# Ethernet_Sheet.net
KiCad netlist of a schematic drawn in Altium Designer
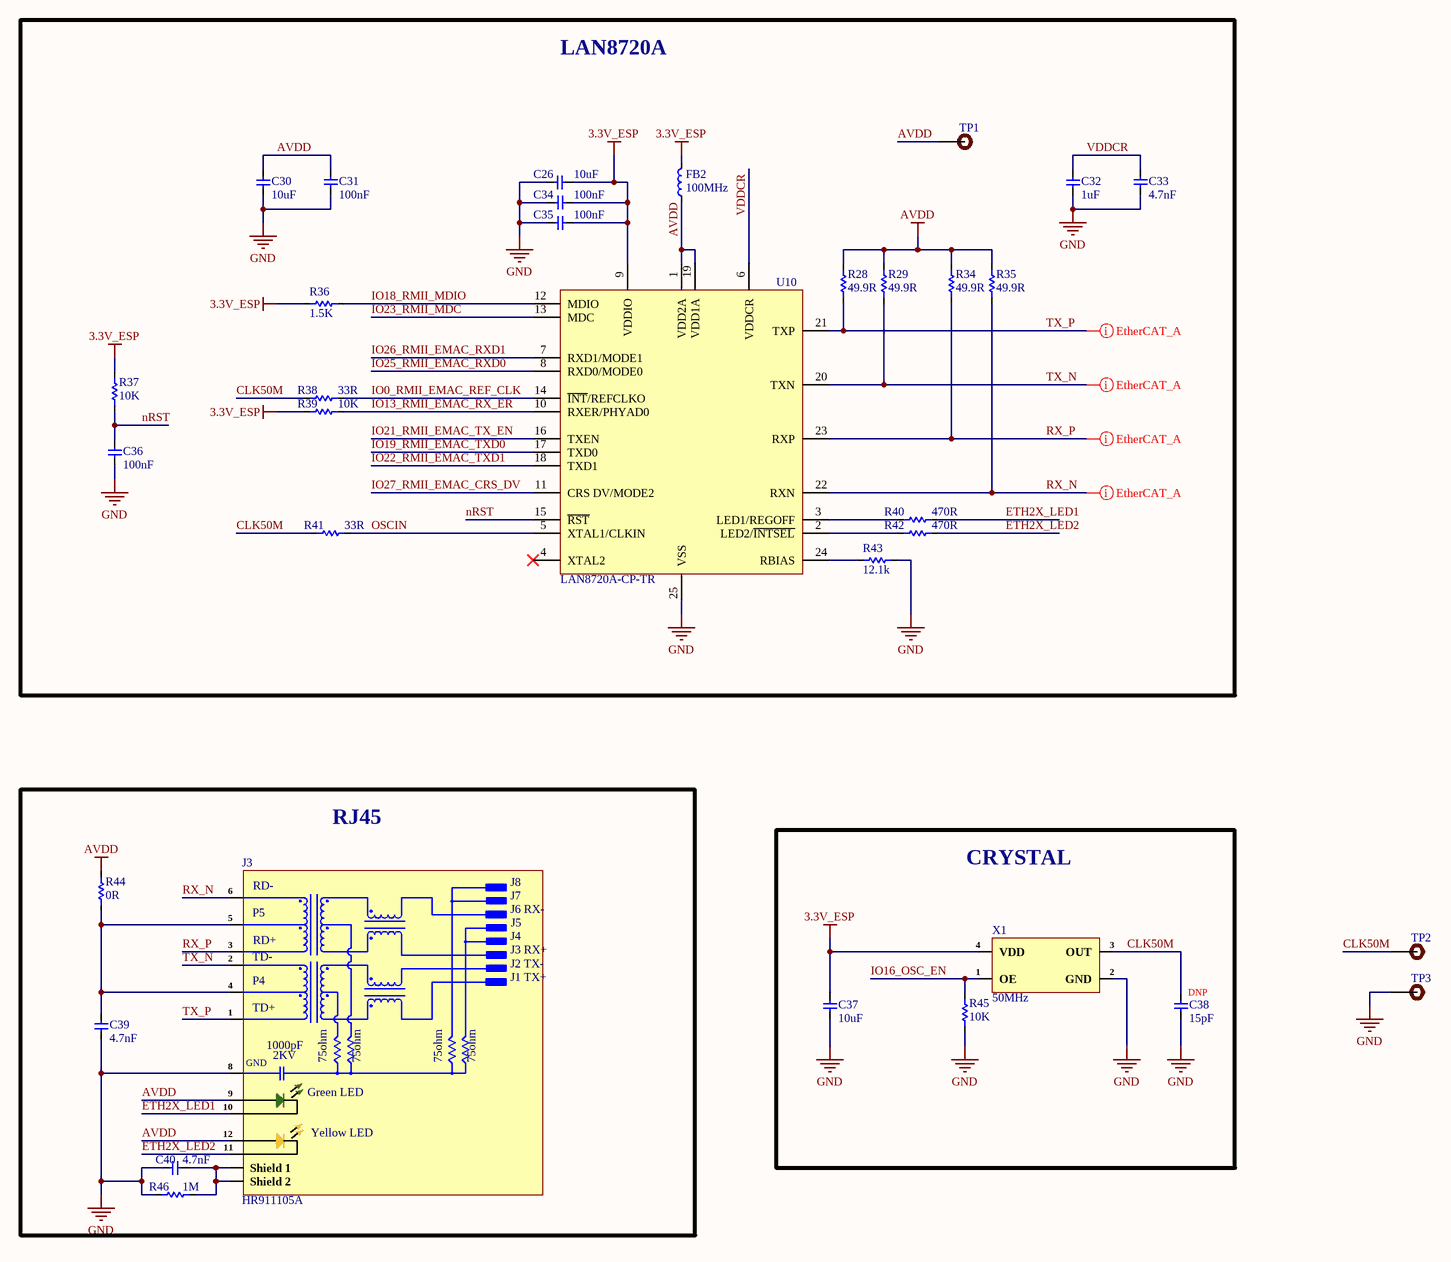
[diagram p0: Ethernet_Sheet.SchDoc]

(export (version "E")
  (design (tool "Eeschema 10.0.6"))
  (components
    (comp (ref "C26")
      (value "10uF")
      (footprint "Cap-0603")
      (description "CAP CER 10UF 25V X5R 0603")
      (fields
        (field (name "MANUFACTURER") "Samsung")
        (field (name "MANUFACTURER PART NUMBER") "CL10A106MA8NRNC")
      )
      (libsource (lib "eSpark Libraries") (part "CL10A106MA8NRNC"))
    )
    (comp (ref "C30")
      (value "10uF")
      (footprint "Cap-0603")
      (description "CAP CER 10UF 25V X5R 0603")
      (fields
        (field (name "MANUFACTURER") "Samsung")
        (field (name "MANUFACTURER PART NUMBER") "CL10A106MA8NRNC")
      )
      (libsource (lib "eSpark Libraries") (part "CL10A106MA8NRNC"))
    )
    (comp (ref "C31")
      (value "100nF")
      (footprint "cap-0402")
      (description "CAP CER 0.1UF 50V X7R 0402")
      (fields
        (field (name "MANUFACTURER") "TDK")
        (field (name "MANUFACTURER PART NUMBER") "C1005X7R1H104KT000F")
      )
      (libsource (lib "eSpark Libraries") (part "C1005X7R1H104KT000F"))
    )
    (comp (ref "C32")
      (value "1uF")
      (footprint "Cap-0402")
      (description "CAP CER 1UF 16V X5R 0402")
      (fields
        (field (name "MANUFACTURER") "Yageo")
        (field (name "MANUFACTURER PART NUMBER") "CC0402KRX5R7BB105")
      )
      (libsource (lib "eSpark Libraries") (part "CC0402KRX5R7BB105"))
    )
    (comp (ref "C33")
      (value "4.7nF")
      (footprint "Cap-0402")
      (description "CAP CER 4700PF 50V X7R 0402")
      (fields
        (field (name "MANUFACTURER") "Yageo")
        (field (name "MANUFACTURER PART NUMBER") "CC0402KRX7R9BB472")
      )
      (libsource (lib "eSpark Libraries") (part "CC0402KRX7R9BB472"))
    )
    (comp (ref "C34")
      (value "100nF")
      (footprint "cap-0402")
      (description "CAP CER 0.1UF 50V X7R 0402")
      (fields
        (field (name "MANUFACTURER") "TDK")
        (field (name "MANUFACTURER PART NUMBER") "C1005X7R1H104KT000F")
      )
      (libsource (lib "eSpark Libraries") (part "C1005X7R1H104KT000F"))
    )
    (comp (ref "C35")
      (value "100nF")
      (footprint "cap-0402")
      (description "CAP CER 0.1UF 50V X7R 0402")
      (fields
        (field (name "MANUFACTURER") "TDK")
        (field (name "MANUFACTURER PART NUMBER") "C1005X7R1H104KT000F")
      )
      (libsource (lib "eSpark Libraries") (part "C1005X7R1H104KT000F"))
    )
    (comp (ref "C36")
      (value "100nF")
      (footprint "cap-0402")
      (description "CAP CER 0.1UF 50V X7R 0402")
      (fields
        (field (name "MANUFACTURER") "TDK")
        (field (name "MANUFACTURER PART NUMBER") "C1005X7R1H104KT000F")
      )
      (libsource (lib "eSpark Libraries") (part "C1005X7R1H104KT000F"))
    )
    (comp (ref "C37")
      (value "10uF")
      (footprint "Cap-0603")
      (description "CAP CER 10UF 25V X5R 0603")
      (fields
        (field (name "MANUFACTURER") "Samsung")
        (field (name "MANUFACTURER PART NUMBER") "CL10A106MA8NRNC")
      )
      (libsource (lib "eSpark Libraries") (part "CL10A106MA8NRNC"))
    )
    (comp (ref "C38")
      (value "15pF")
      (footprint "Cap-0603")
      (description "CAP CER 15PF 50V C0G/NPO 0603")
      (fields
        (field (name "MANUFACTURER") "Yageo")
        (field (name "MANUFACTURER PART NUMBER") "CC0603JRNPO9BN150")
      )
      (libsource (lib "eSpark Libraries") (part "CC0603JRNPO9BN150"))
    )
    (comp (ref "C39")
      (value "4.7nF")
      (footprint "Cap-0402")
      (description "CAP CER 4700PF 50V X7R 0402")
      (fields
        (field (name "MANUFACTURER") "Yageo")
        (field (name "MANUFACTURER PART NUMBER") "CC0402KRX7R9BB472")
      )
      (libsource (lib "eSpark Libraries") (part "CC0402KRX7R9BB472"))
    )
    (comp (ref "C40")
      (value "4.7nF")
      (footprint "Cap-1206")
      (description "CAP CER 4700PF 1KV X7R 1206")
      (fields
        (field (name "MANUFACTURER") "Yageo")
        (field (name "MANUFACTURER PART NUMBER") "CC1206KKX7RCBB472")
      )
      (libsource (lib "eSpark Libraries") (part "CC1206KKX7RCBB472"))
    )
    (comp (ref "FB2")
      (value "100MHz")
      (footprint "IND-1206")
      (description "FERRITE BEAD 120 OHM 1206 1LN")
      (fields
        (field (name "MANUFACTURER") "Murata")
        (field (name "MANUFACTURER PART NUMBER") "BLM31PG121SN1L")
      )
      (libsource (lib "eSpark Libraries") (part "BLM31PG121SN1L"))
    )
    (comp (ref "J3")
      (value "HR911105A")
      (footprint "HR911105A")
      (description "RJ45 RJReceptacle 1 WithLED Plugin Ethernet Connectors/Modular Connectors (RJ45 RJ11) ROHS")
      (fields (field (name "MANUFACTURER") "HANRUN") (field (name "LCSC PART NUMBER") "C12074"))
      (libsource (lib "eSpark Libraries") (part "HR911105A"))
    )
    (comp (ref "R28")
      (value "49.9R")
      (footprint "Res-0402")
      (description "49.9Ω 62.5mW 50V ±100ppm/℃ Thick Film Resistor ±1% 0402 Chip Resistor - Surface Mount ROHS")
      (fields
        (field (name "MANUFACTURER") "YAGEO")
        (field (name "MANUFACTURER PART NUMBER") "RC0402FR-0749R9L")
      )
      (libsource (lib "eSpark Libraries") (part "RC0402FR-0749R9L"))
    )
    (comp (ref "R29")
      (value "49.9R")
      (footprint "Res-0402")
      (description "49.9Ω 62.5mW 50V ±100ppm/℃ Thick Film Resistor ±1% 0402 Chip Resistor - Surface Mount ROHS")
      (fields
        (field (name "MANUFACTURER") "YAGEO")
        (field (name "MANUFACTURER PART NUMBER") "RC0402FR-0749R9L")
      )
      (libsource (lib "eSpark Libraries") (part "RC0402FR-0749R9L"))
    )
    (comp (ref "R34")
      (value "49.9R")
      (footprint "Res-0402")
      (description "49.9Ω 62.5mW 50V ±100ppm/℃ Thick Film Resistor ±1% 0402 Chip Resistor - Surface Mount ROHS")
      (fields
        (field (name "MANUFACTURER") "YAGEO")
        (field (name "MANUFACTURER PART NUMBER") "RC0402FR-0749R9L")
      )
      (libsource (lib "eSpark Libraries") (part "RC0402FR-0749R9L"))
    )
    (comp (ref "R35")
      (value "49.9R")
      (footprint "Res-0402")
      (description "49.9Ω 62.5mW 50V ±100ppm/℃ Thick Film Resistor ±1% 0402 Chip Resistor - Surface Mount ROHS")
      (fields
        (field (name "MANUFACTURER") "YAGEO")
        (field (name "MANUFACTURER PART NUMBER") "RC0402FR-0749R9L")
      )
      (libsource (lib "eSpark Libraries") (part "RC0402FR-0749R9L"))
    )
    (comp (ref "R36")
      (value "1.5K")
      (footprint "Res-0402")
      (description "RES 1.5K OHM 1% 1/16W 0402")
      (fields
        (field (name "MANUFACTURER") "Yageo")
        (field (name "MANUFACTURER PART NUMBER") "RC0402FR-071K5L")
      )
      (libsource (lib "eSpark Libraries") (part "RC0402FR-071K5L"))
    )
    (comp (ref "R37")
      (value "10K")
      (footprint "Res-0402")
      (description "RES 10K OHM 1% 1/16W 0402")
      (fields
        (field (name "MANUFACTURER") "Yageo")
        (field (name "MANUFACTURER PART NUMBER") "RC0402FR-0710KL")
      )
      (libsource (lib "eSpark Libraries") (part "RC0402FR-0710KL"))
    )
    (comp (ref "R38")
      (value "33R")
      (footprint "Res-0402")
      (description "RES 33 OHM 1% 1/16W 0402")
      (fields
        (field (name "MANUFACTURER") "Yageo")
        (field (name "MANUFACTURER PART NUMBER") "RC0402FR-0733RL")
      )
      (libsource (lib "eSpark Libraries") (part "RC0402FR-0733RL"))
    )
    (comp (ref "R39")
      (value "10K")
      (footprint "Res-0402")
      (description "RES 10K OHM 1% 1/16W 0402")
      (fields
        (field (name "MANUFACTURER") "Yageo")
        (field (name "MANUFACTURER PART NUMBER") "RC0402FR-0710KL")
      )
      (libsource (lib "eSpark Libraries") (part "RC0402FR-0710KL"))
    )
    (comp (ref "R40")
      (value "470R")
      (footprint "Res-0402")
      (description "RES 470 OHM 1% 1/16W 0402")
      (fields
        (field (name "MANUFACTURER") "Yageo")
        (field (name "MANUFACTURER PART NUMBER") "RC0402FR-07470RL")
      )
      (libsource (lib "eSpark Libraries") (part "RC0402FR-07470RL"))
    )
    (comp (ref "R41")
      (value "33R")
      (footprint "Res-0402")
      (description "RES 33 OHM 1% 1/16W 0402")
      (fields
        (field (name "MANUFACTURER") "Yageo")
        (field (name "MANUFACTURER PART NUMBER") "RC0402FR-0733RL")
      )
      (libsource (lib "eSpark Libraries") (part "RC0402FR-0733RL"))
    )
    (comp (ref "R42")
      (value "470R")
      (footprint "Res-0402")
      (description "RES 470 OHM 1% 1/16W 0402")
      (fields
        (field (name "MANUFACTURER") "Yageo")
        (field (name "MANUFACTURER PART NUMBER") "RC0402FR-07470RL")
      )
      (libsource (lib "eSpark Libraries") (part "RC0402FR-07470RL"))
    )
    (comp (ref "R43")
      (value "12.1k")
      (footprint "Res-0402")
      (description "RES SMD 12.1KOHM 0.1% 1/16W 0402")
      (fields
        (field (name "MANUFACTURER") "Yageo")
        (field (name "MANUFACTURER PART NUMBER") "RT0402BRD0712K1L")
      )
      (libsource (lib "eSpark Libraries") (part "RT0402BRD0712K1L"))
    )
    (comp (ref "R44")
      (value "0R")
      (footprint "Res-0402")
      (description "RES 0 OHM JUMPER 1/16W 0402")
      (fields
        (field (name "MANUFACTURER") "Yageo")
        (field (name "MANUFACTURER PART NUMBER") "RC0402FR-070RL")
      )
      (libsource (lib "eSpark Libraries") (part "RC0402FR-070RL"))
    )
    (comp (ref "R45")
      (value "10K")
      (footprint "Res-0402")
      (description "RES 10K OHM 1% 1/16W 0402")
      (fields
        (field (name "MANUFACTURER") "Yageo")
        (field (name "MANUFACTURER PART NUMBER") "RC0402FR-0710KL")
      )
      (libsource (lib "eSpark Libraries") (part "RC0402FR-0710KL"))
    )
    (comp (ref "R46")
      (value "1M")
      (footprint "Res-1206")
      (description "RES 1M OHM 1% 1/4W 1206")
      (fields
        (field (name "MANUFACTURER") "Yageo")
        (field (name "MANUFACTURER PART NUMBER") "RC1206FR-071ML")
      )
      (libsource (lib "eSpark Libraries") (part "RC1206FR-071ML"))
    )
    (comp (ref "TP1")
      (value "TEST POINT 0.5mm Dia")
      (footprint "Test-point - 0.5mm")
      (description "Test Point ON")
      (libsource (lib "eSpark Libraries") (part "TEST POINT 0.5mm Dia"))
    )
    (comp (ref "TP2")
      (value "TEST POINT 0.5mm Dia")
      (footprint "Test-point - 0.5mm")
      (description "Test Point ON")
      (libsource (lib "eSpark Libraries") (part "TEST POINT 0.5mm Dia"))
    )
    (comp (ref "TP3")
      (value "TEST POINT 0.5mm Dia")
      (footprint "Test-point - 0.5mm")
      (description "Test Point ON")
      (libsource (lib "eSpark Libraries") (part "TEST POINT 0.5mm Dia"))
    )
    (comp (ref "U10")
      (value "LAN8720A-CP-TR")
      (footprint "LAN8720A-CP-TR")
      (description "IC TRANSCEIVER FULL 2/2 24SQFN")
      (fields (field (name "MANUFACTURER") "MICROCHIP") (field (name "LCSC PART NUMBER") "C45223"))
      (libsource (lib "eSpark Libraries") (part "LAN8720A-CP-TR"))
    )
    (comp (ref "X1")
      (value "50MHz")
      (footprint "OT2EL4C4JI-111OLP-50M")
      (description "1.8V~3.3V ±10ppm ±20ppm CMOS 50MHz SMD3225-4P Crystal Oscillators ROHS")
      (fields
        (field (name "MANUFACTURER") "YXC Crystal Oscillators")
        (field (name "MANUFACTURER PART NUMBER") "OT2EL4C4JI-111OLP-50M")
      )
      (libsource (lib "eSpark Libraries") (part "OT2EL4C4JI-111OLP-50M"))
    )
  )
  (nets
    (net (code "1") (name "/CLK50M") (class "Default")
      (node (ref "C38") (pin "2") (pinfunction "2_2") (pintype "passive"))
      (node (ref "R38") (pin "1") (pinfunction "1_1") (pintype "passive"))
      (node (ref "R41") (pin "1") (pinfunction "1_1") (pintype "passive"))
      (node (ref "TP2") (pin "1") (pinfunction "1_1") (pintype "passive"))
      (node (ref "X1") (pin "3") (pinfunction "OUT_3") (pintype "passive"))
    )
    (net (code "2") (name "/ETH2X_LED1") (class "Default")
      (node (ref "J3") (pin "10") (pinfunction "CATHODE_10") (pintype "passive"))
      (node (ref "R40") (pin "2") (pinfunction "2_2") (pintype "passive"))
    )
    (net (code "3") (name "/ETH2X_LED2") (class "Default")
      (node (ref "J3") (pin "11") (pinfunction "CATHODE_11") (pintype "passive"))
      (node (ref "R42") (pin "2") (pinfunction "2_2") (pintype "passive"))
    )
    (net (code "4") (name "/IO0_RMII_EMAC_REF_CLK") (class "Default")
      (node (ref "R38") (pin "2") (pinfunction "2_2") (pintype "passive"))
      (node (ref "U10") (pin "14") (pinfunction "~{INT}/REFCLKO_14") (pintype "passive"))
    )
    (net (code "5") (name "/IO13_RMII_EMAC_RX_ER") (class "Default")
      (node (ref "R39") (pin "1") (pinfunction "1_1") (pintype "passive"))
      (node (ref "U10") (pin "10") (pinfunction "RXER/PHYAD0_10") (pintype "passive"))
    )
    (net (code "6") (name "/IO16_OSC_EN") (class "Default")
      (node (ref "R45") (pin "1") (pinfunction "1_1") (pintype "passive"))
      (node (ref "X1") (pin "1") (pinfunction "OE_1") (pintype "passive"))
    )
    (net (code "7") (name "/IO18_RMII_MDIO") (class "Default")
      (node (ref "R36") (pin "1") (pinfunction "1_1") (pintype "passive"))
      (node (ref "U10") (pin "12") (pinfunction "MDIO_12") (pintype "passive"))
    )
    (net (code "8") (name "/IO19_RMII_EMAC_TXD0") (class "Default")
      (node (ref "U10") (pin "17") (pinfunction "TXD0_17") (pintype "passive"))
    )
    (net (code "9") (name "/IO21_RMII_EMAC_TX_EN") (class "Default")
      (node (ref "U10") (pin "16") (pinfunction "TXEN_16") (pintype "passive"))
    )
    (net (code "10") (name "/IO22_RMII_EMAC_TXD1") (class "Default")
      (node (ref "U10") (pin "18") (pinfunction "TXD1_18") (pintype "passive"))
    )
    (net (code "11") (name "/IO23_RMII_MDC") (class "Default")
      (node (ref "U10") (pin "13") (pinfunction "MDC_13") (pintype "passive"))
    )
    (net (code "12") (name "/IO25_RMII_EMAC_RXD0") (class "Default")
      (node (ref "U10") (pin "8") (pinfunction "RXD0/MODE0_8") (pintype "passive"))
    )
    (net (code "13") (name "/IO26_RMII_EMAC_RXD1") (class "Default")
      (node (ref "U10") (pin "7") (pinfunction "RXD1/MODE1_7") (pintype "passive"))
    )
    (net (code "14") (name "/IO27_RMII_EMAC_CRS_DV") (class "Default")
      (node (ref "U10") (pin "11") (pinfunction "CRS_DV/MODE2_11") (pintype "passive"))
    )
    (net (code "15") (name "/OSCIN") (class "Default")
      (node (ref "R41") (pin "2") (pinfunction "2_2") (pintype "passive"))
      (node (ref "U10") (pin "5") (pinfunction "XTAL1/CLKIN_5") (pintype "passive"))
    )
    (net (code "16") (name "/RX_N") (class "Default")
      (node (ref "J3") (pin "6") (pinfunction "RD-_6") (pintype "passive"))
      (node (ref "R35") (pin "1") (pinfunction "1_1") (pintype "passive"))
      (node (ref "U10") (pin "22") (pinfunction "RXN_22") (pintype "passive"))
    )
    (net (code "17") (name "/RX_P") (class "Default")
      (node (ref "J3") (pin "3") (pinfunction "RD+_3") (pintype "passive"))
      (node (ref "R34") (pin "1") (pinfunction "1_1") (pintype "passive"))
      (node (ref "U10") (pin "23") (pinfunction "RXP_23") (pintype "passive"))
    )
    (net (code "18") (name "/TX_N") (class "Default")
      (node (ref "J3") (pin "2") (pinfunction "TD-_2") (pintype "passive"))
      (node (ref "R29") (pin "1") (pinfunction "1_1") (pintype "passive"))
      (node (ref "U10") (pin "20") (pinfunction "TXN_20") (pintype "passive"))
    )
    (net (code "19") (name "/TX_P") (class "Default")
      (node (ref "J3") (pin "1") (pinfunction "TD+_1") (pintype "passive"))
      (node (ref "R28") (pin "1") (pinfunction "1_1") (pintype "passive"))
      (node (ref "U10") (pin "21") (pinfunction "TXP_21") (pintype "passive"))
    )
    (net (code "20") (name "/VDDCR") (class "Default")
      (node (ref "C32") (pin "2") (pinfunction "2_2") (pintype "passive"))
      (node (ref "C33") (pin "1") (pinfunction "1_1") (pintype "passive"))
      (node (ref "U10") (pin "6") (pinfunction "VDDCR_6") (pintype "passive"))
    )
    (net (code "21") (name "/nRST") (class "Default")
      (node (ref "C36") (pin "2") (pinfunction "2_2") (pintype "passive"))
      (node (ref "R37") (pin "1") (pinfunction "1_1") (pintype "passive"))
      (node (ref "U10") (pin "15") (pinfunction "~{RST}_15") (pintype "passive"))
    )
    (net (code "22") (name "3.3V_ESP") (class "Default")
      (node (ref "C26") (pin "2") (pinfunction "2_2") (pintype "passive"))
      (node (ref "C34") (pin "1") (pinfunction "1_1") (pintype "passive"))
      (node (ref "C35") (pin "1") (pinfunction "1_1") (pintype "passive"))
      (node (ref "C37") (pin "2") (pinfunction "2_2") (pintype "passive"))
      (node (ref "FB2") (pin "2") (pinfunction "2_2") (pintype "passive"))
      (node (ref "R36") (pin "2") (pinfunction "2_2") (pintype "passive"))
      (node (ref "R37") (pin "2") (pinfunction "2_2") (pintype "passive"))
      (node (ref "R39") (pin "2") (pinfunction "2_2") (pintype "passive"))
      (node (ref "U10") (pin "9") (pinfunction "VDDIO_9") (pintype "passive"))
      (node (ref "X1") (pin "4") (pinfunction "VDD_4") (pintype "passive"))
    )
    (net (code "23") (name "AVDD") (class "Default")
      (node (ref "C30") (pin "2") (pinfunction "2_2") (pintype "passive"))
      (node (ref "C31") (pin "1") (pinfunction "1_1") (pintype "passive"))
      (node (ref "FB2") (pin "1") (pinfunction "1_1") (pintype "passive"))
      (node (ref "J3") (pin "12") (pinfunction "ANODE_12") (pintype "passive"))
      (node (ref "J3") (pin "9") (pinfunction "ANODE_9") (pintype "passive"))
      (node (ref "R28") (pin "2") (pinfunction "2_2") (pintype "passive"))
      (node (ref "R29") (pin "2") (pinfunction "2_2") (pintype "passive"))
      (node (ref "R34") (pin "2") (pinfunction "2_2") (pintype "passive"))
      (node (ref "R35") (pin "2") (pinfunction "2_2") (pintype "passive"))
      (node (ref "R44") (pin "2") (pinfunction "2_2") (pintype "passive"))
      (node (ref "TP1") (pin "1") (pinfunction "1_1") (pintype "passive"))
      (node (ref "U10") (pin "1") (pinfunction "VDD2A_1") (pintype "passive"))
      (node (ref "U10") (pin "19") (pinfunction "VDD1A_19") (pintype "passive"))
    )
    (net (code "24") (name "GND") (class "Default")
      (node (ref "C26") (pin "1") (pinfunction "1_1") (pintype "passive"))
      (node (ref "C30") (pin "1") (pinfunction "1_1") (pintype "passive"))
      (node (ref "C31") (pin "2") (pinfunction "2_2") (pintype "passive"))
      (node (ref "C32") (pin "1") (pinfunction "1_1") (pintype "passive"))
      (node (ref "C33") (pin "2") (pinfunction "2_2") (pintype "passive"))
      (node (ref "C34") (pin "2") (pinfunction "2_2") (pintype "passive"))
      (node (ref "C35") (pin "2") (pinfunction "2_2") (pintype "passive"))
      (node (ref "C36") (pin "1") (pinfunction "1_1") (pintype "passive"))
      (node (ref "C37") (pin "1") (pinfunction "1_1") (pintype "passive"))
      (node (ref "C38") (pin "1") (pinfunction "1_1") (pintype "passive"))
      (node (ref "C39") (pin "1") (pinfunction "1_1") (pintype "passive"))
      (node (ref "C40") (pin "1") (pinfunction "1_1") (pintype "passive"))
      (node (ref "J3") (pin "8") (pinfunction "GND_8") (pintype "power_in"))
      (node (ref "R43") (pin "1") (pinfunction "1_1") (pintype "passive"))
      (node (ref "R45") (pin "2") (pinfunction "2_2") (pintype "passive"))
      (node (ref "R46") (pin "1") (pinfunction "1_1") (pintype "passive"))
      (node (ref "TP3") (pin "1") (pinfunction "1_1") (pintype "passive"))
      (node (ref "U10") (pin "25") (pinfunction "VSS_25") (pintype "passive"))
      (node (ref "X1") (pin "2") (pinfunction "GND_2") (pintype "passive"))
    )
    (net (code "25") (name "Net-(C40-Pad2)") (class "Default")
      (node (ref "C40") (pin "2") (pinfunction "2_2") (pintype "passive"))
      (node (ref "J3") (pin "Shield_1") (pinfunction "Shield_1_Shield_1") (pintype "passive"))
      (node (ref "J3") (pin "Shield_2") (pinfunction "Shield_2_Shield_2") (pintype "passive"))
      (node (ref "R46") (pin "2") (pinfunction "2_2") (pintype "passive"))
    )
    (net (code "26") (name "Net-(J3-P4)") (class "Default")
      (node (ref "C39") (pin "2") (pinfunction "2_2") (pintype "passive"))
      (node (ref "J3") (pin "4") (pinfunction "P4_4") (pintype "passive"))
      (node (ref "J3") (pin "5") (pinfunction "P5_5") (pintype "passive"))
      (node (ref "R44") (pin "1") (pinfunction "1_1") (pintype "passive"))
    )
    (net (code "27") (name "Net-(U10-LED1{slash}REGOFF)") (class "Default")
      (node (ref "R40") (pin "1") (pinfunction "1_1") (pintype "passive"))
      (node (ref "U10") (pin "3") (pinfunction "LED1/REGOFF_3") (pintype "passive"))
    )
    (net (code "28") (name "Net-(U10-LED2{slash}~{INTSEL})") (class "Default")
      (node (ref "R42") (pin "1") (pinfunction "1_1") (pintype "passive"))
      (node (ref "U10") (pin "2") (pinfunction "LED2/~{INTSEL}_2") (pintype "passive"))
    )
    (net (code "29") (name "Net-(U10-RBIAS)") (class "Default")
      (node (ref "R43") (pin "2") (pinfunction "2_2") (pintype "passive"))
      (node (ref "U10") (pin "24") (pinfunction "RBIAS_24") (pintype "passive"))
    )
    (net (code "30") (name "unconnected-(U10-XTAL2-Pad4)") (class "Default")
      (node (ref "U10") (pin "4") (pinfunction "XTAL2_4") (pintype "passive+no_connect"))
    )
  )
)
